# LaunchFET-iso.net
KiCad netlist of a schematic drawn in EAGLE
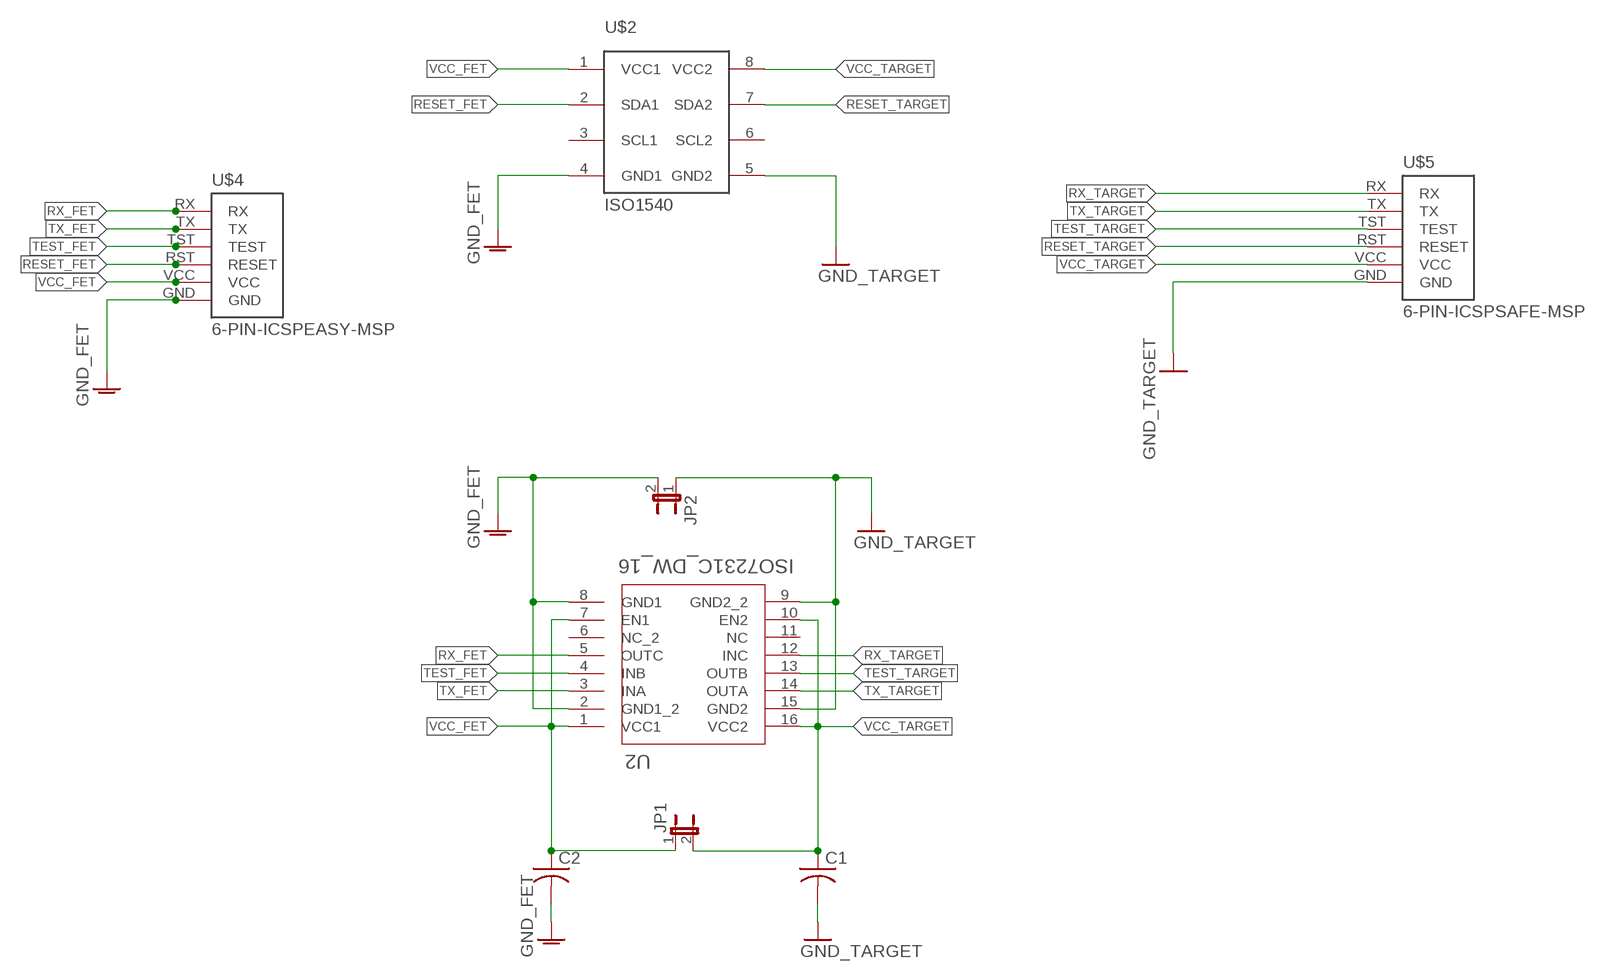
[diagram p0: schematic, sheet 1]

(export (version "E")
  (design (tool "Eeschema 10.0.6"))
  (components
    (comp (ref "C1")
      (value "C-USC1206")
      (footprint "eagle-import:C1206")
      (libsource (lib "eagle-import") (part "C-USC1206"))
    )
    (comp (ref "C2")
      (value "C-USC1206")
      (footprint "eagle-import:C1206")
      (libsource (lib "eagle-import") (part "C-USC1206"))
    )
    (comp (ref "JP1")
      (value "JUMPER-2PTH_LOCK")
      (footprint "eagle-import:1X02_LOCK")
      (libsource (lib "eagle-import") (part "JUMPER-2PTH_LOCK"))
    )
    (comp (ref "JP2")
      (value "JUMPER-2PTH_LOCK")
      (footprint "eagle-import:1X02_LOCK")
      (libsource (lib "eagle-import") (part "JUMPER-2PTH_LOCK"))
    )
    (comp (ref "U$2")
      (value "ISO1540")
      (footprint "eagle-import:D8")
      (libsource (lib "eagle-import") (part "ISO1540"))
    )
    (comp (ref "U$4")
      (value "6-PIN-ICSPEASY-MSP")
      (footprint "eagle-import:EASYMSP-6PIN")
      (libsource (lib "eagle-import") (part "6-PIN-ICSPEASY-MSP"))
    )
    (comp (ref "U$5")
      (value "6-PIN-ICSPSAFE-MSP")
      (footprint "eagle-import:SAFEMSP-6PIN")
      (libsource (lib "eagle-import") (part "6-PIN-ICSPSAFE-MSP"))
    )
    (comp (ref "U2")
      (value "ISO7231C_DW_16")
      (footprint "eagle-import:DW16")
      (fields
        (field (name "GENERIC_PART_NUMBER") "ISO7231C")
        (field (name "MANUFACTURER") "Texas Instruments")
        (field (name "MANUFACTURER_PART_NUMBER") "iso7231c_dw_16")
      )
      (libsource (lib "eagle-import") (part "ISO7231C_DW_16"))
    )
  )
  (nets
    (net (code "1") (name "GND_FET") (class "Default")
      (node (ref "C2") (pin "2") (pinfunction "2_2") (pintype "passive"))
      (node (ref "JP2") (pin "2") (pinfunction "2_2") (pintype "passive"))
      (node (ref "U$2") (pin "4") (pinfunction "GND1_4") (pintype "bidirectional"))
      (node (ref "U$4") (pin "GND") (pinfunction "GND_GND") (pintype "bidirectional"))
      (node (ref "U2") (pin "2") (pinfunction "GND1_2_2") (pintype "power_in"))
      (node (ref "U2") (pin "8") (pinfunction "GND1_8") (pintype "power_in"))
    )
    (net (code "2") (name "GND_TARGET") (class "Default")
      (node (ref "C1") (pin "2") (pinfunction "2_2") (pintype "passive"))
      (node (ref "JP2") (pin "1") (pinfunction "1_1") (pintype "passive"))
      (node (ref "U$2") (pin "5") (pinfunction "GND2_5") (pintype "bidirectional"))
      (node (ref "U$5") (pin "GND") (pinfunction "GND_GND") (pintype "bidirectional"))
      (node (ref "U2") (pin "15") (pinfunction "GND2_15") (pintype "power_in"))
      (node (ref "U2") (pin "9") (pinfunction "GND2_2_9") (pintype "power_in"))
    )
    (net (code "3") (name "RESET_FET") (class "Default")
      (node (ref "U$2") (pin "2") (pinfunction "SDA1_2") (pintype "bidirectional"))
      (node (ref "U$4") (pin "RST") (pinfunction "RESET_RST") (pintype "bidirectional"))
    )
    (net (code "4") (name "RESET_TARGET") (class "Default")
      (node (ref "U$2") (pin "7") (pinfunction "SDA2_7") (pintype "bidirectional"))
      (node (ref "U$5") (pin "RST") (pinfunction "RESET_RST") (pintype "bidirectional"))
    )
    (net (code "5") (name "RX_FET") (class "Default")
      (node (ref "U$4") (pin "RX") (pinfunction "RX_RX") (pintype "bidirectional"))
      (node (ref "U2") (pin "5") (pinfunction "OUTC_5") (pintype "output"))
    )
    (net (code "6") (name "RX_TARGET") (class "Default")
      (node (ref "U$5") (pin "RX") (pinfunction "RX_RX") (pintype "bidirectional"))
      (node (ref "U2") (pin "12") (pinfunction "INC_12") (pintype "input"))
    )
    (net (code "7") (name "TEST_FET") (class "Default")
      (node (ref "U$4") (pin "TST") (pinfunction "TEST_TST") (pintype "bidirectional"))
      (node (ref "U2") (pin "4") (pinfunction "INB_4") (pintype "input"))
    )
    (net (code "8") (name "TEST_TARGET") (class "Default")
      (node (ref "U$5") (pin "TST") (pinfunction "TEST_TST") (pintype "bidirectional"))
      (node (ref "U2") (pin "13") (pinfunction "OUTB_13") (pintype "output"))
    )
    (net (code "9") (name "TX_FET") (class "Default")
      (node (ref "U$4") (pin "TX") (pinfunction "TX_TX") (pintype "bidirectional"))
      (node (ref "U2") (pin "3") (pinfunction "INA_3") (pintype "input"))
    )
    (net (code "10") (name "TX_TARGET") (class "Default")
      (node (ref "U$5") (pin "TX") (pinfunction "TX_TX") (pintype "bidirectional"))
      (node (ref "U2") (pin "14") (pinfunction "OUTA_14") (pintype "output"))
    )
    (net (code "11") (name "VCC_FET") (class "Default")
      (node (ref "C2") (pin "1") (pinfunction "1_1") (pintype "passive"))
      (node (ref "JP1") (pin "1") (pinfunction "1_1") (pintype "passive"))
      (node (ref "U$2") (pin "1") (pinfunction "VCC1_1") (pintype "bidirectional"))
      (node (ref "U$4") (pin "VCC") (pinfunction "VCC_VCC") (pintype "bidirectional"))
      (node (ref "U2") (pin "1") (pinfunction "VCC1_1") (pintype "power_in"))
      (node (ref "U2") (pin "7") (pinfunction "EN1_7") (pintype "passive"))
    )
    (net (code "12") (name "VCC_TARGET") (class "Default")
      (node (ref "C1") (pin "1") (pinfunction "1_1") (pintype "passive"))
      (node (ref "JP1") (pin "2") (pinfunction "2_2") (pintype "passive"))
      (node (ref "U$2") (pin "8") (pinfunction "VCC2_8") (pintype "bidirectional"))
      (node (ref "U$5") (pin "VCC") (pinfunction "VCC_VCC") (pintype "bidirectional"))
      (node (ref "U2") (pin "10") (pinfunction "EN2_10") (pintype "passive"))
      (node (ref "U2") (pin "16") (pinfunction "VCC2_16") (pintype "power_in"))
    )
    (net (code "13") (name "unconnected-(U$2-SCL1-Pad3)") (class "Default")
      (node (ref "U$2") (pin "3") (pinfunction "SCL1_3") (pintype "bidirectional"))
    )
    (net (code "14") (name "unconnected-(U$2-SCL2-Pad6)") (class "Default")
      (node (ref "U$2") (pin "6") (pinfunction "SCL2_6") (pintype "bidirectional"))
    )
    (net (code "15") (name "unconnected-(U2-NC-Pad11)") (class "Default")
      (node (ref "U2") (pin "11") (pinfunction "NC_11") (pintype "passive"))
    )
    (net (code "16") (name "unconnected-(U2-NC_2-Pad6)") (class "Default")
      (node (ref "U2") (pin "6") (pinfunction "NC_2_6") (pintype "passive"))
    )
  )
)
